# NodoFinalTbeam.net
KiCad netlist of a schematic drawn in Altium Designer
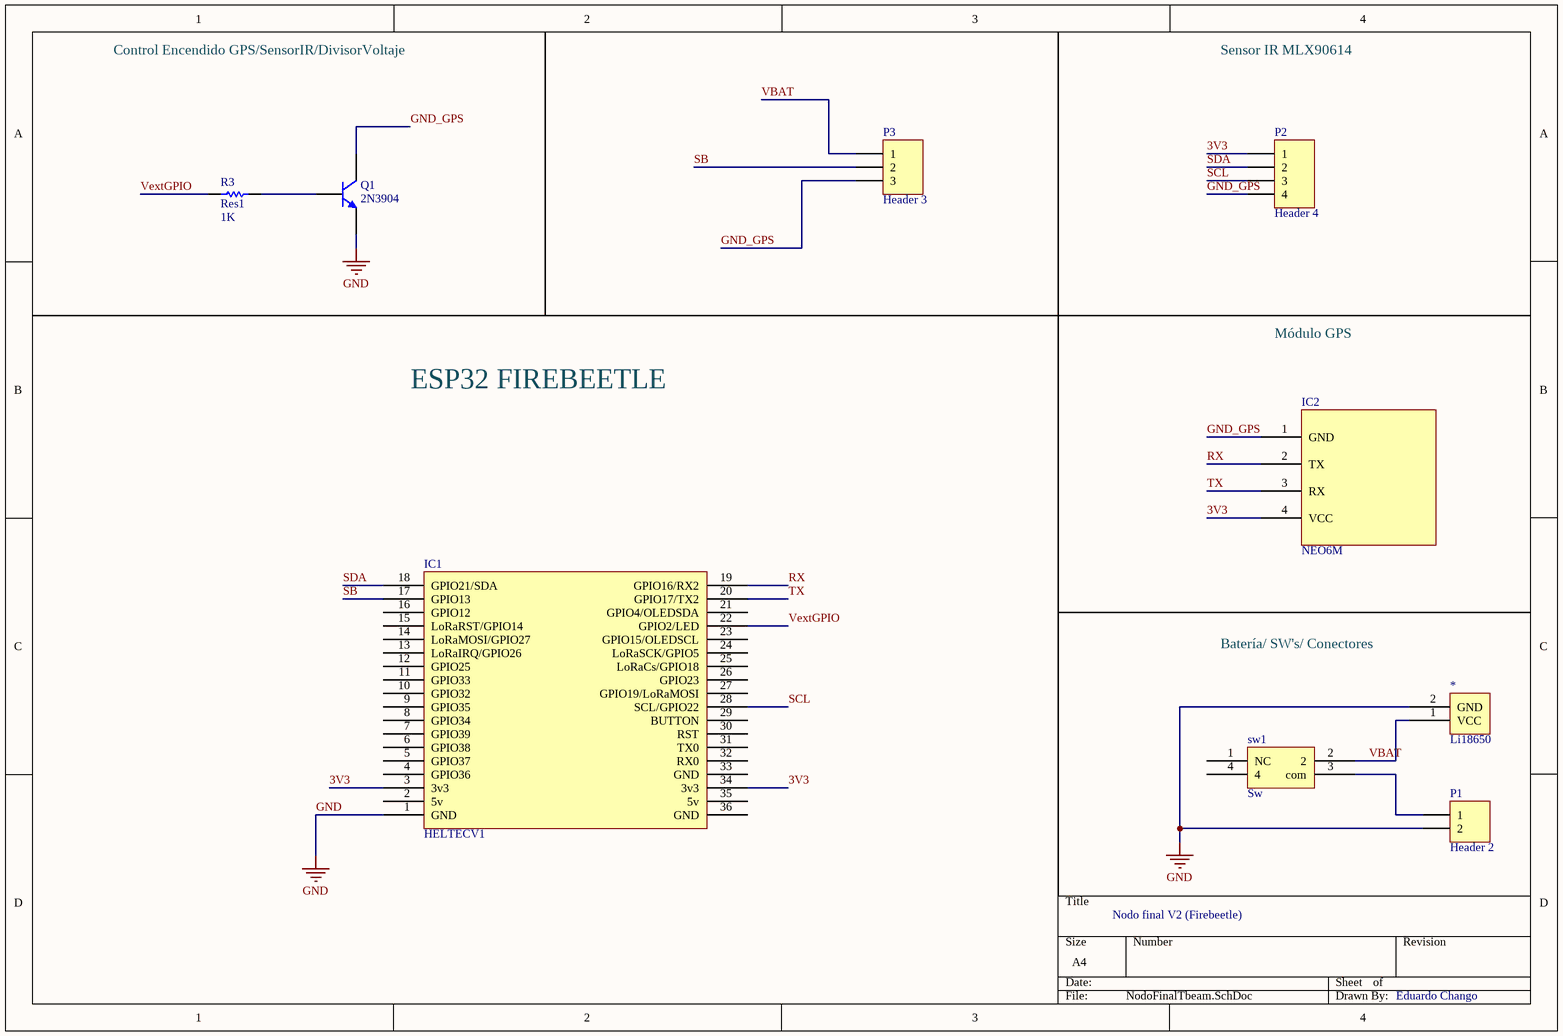
[diagram p0: NodoFinalTbeam.SchDoc]

(export (version "E")
  (design (tool "Eeschema 10.0.6"))
  (components
    (comp (ref "*")
      (value "Li18650")
      (footprint "Li18650")
      (libsource (lib "ComponentesTesis") (part "Li18650"))
    )
    (comp (ref "IC1")
      (value "HELTECV1")
      (footprint "HELTECV1")
      (description "ESP32 LORA BASED MCU")
      (libsource (lib "ComponentesTesis") (part "HELTECV1"))
    )
    (comp (ref "IC2")
      (value "NEO6M")
      (footprint "NEO6M")
      (description "GPS NEO6M")
      (libsource (lib "ComponentesTesis") (part "NEO6M"))
    )
    (comp (ref "P1")
      (value "Header 2")
      (footprint "HDR1X2")
      (description "Header, 2-Pin")
      (fields (field (name "PUBLISHER") "Altium Limited"))
      (libsource (lib "Miscellaneous Connectors") (part "Header 2"))
    )
    (comp (ref "P2")
      (value "Header 4")
      (footprint "HDR1X4")
      (description "Header, 4-Pin")
      (fields (field (name "PUBLISHER") "Altium Limited"))
      (libsource (lib "Miscellaneous Connectors") (part "Header 4"))
    )
    (comp (ref "P3")
      (value "Header 3")
      (footprint "HDR1X3")
      (description "Header, 3-Pin")
      (fields (field (name "PUBLISHER") "Altium Limited"))
      (libsource (lib "Miscellaneous Connectors") (part "Header 3"))
    )
    (comp (ref "Q1")
      (value "2N3904")
      (footprint "TO-92A")
      (description "NPN General Purpose Amplifier")
      (fields (field (name "PUBLISHER") "Altium Limited"))
      (libsource (lib "Miscellaneous Devices") (part "2N3904"))
    )
    (comp (ref "R3")
      (value "Res1")
      (footprint "AXIAL-0.3")
      (description "Resistor")
      (fields (field (name "ALTIUM_VALUE") "1K") (field (name "PUBLISHER") "Altium Limited"))
      (libsource (lib "Miscellaneous Devices") (part "Res1"))
    )
    (comp (ref "sw1")
      (value "Sw")
      (footprint "InterruptorSMD")
      (libsource (lib "ComponentesTesis") (part "Sw"))
    )
  )
  (nets
    (net (code "1") (name "/3V3") (class "Default")
      (node (ref "IC1") (pin "3") (pinfunction "3v3_3") (pintype "power_in"))
      (node (ref "IC1") (pin "34") (pinfunction "3v3_34") (pintype "power_in"))
      (node (ref "IC2") (pin "4") (pinfunction "VCC_4") (pintype "passive"))
      (node (ref "P2") (pin "1") (pinfunction "1_1") (pintype "passive"))
    )
    (net (code "2") (name "/GND_GPS") (class "Default")
      (node (ref "IC2") (pin "1") (pinfunction "GND_1") (pintype "power_in"))
      (node (ref "P2") (pin "4") (pinfunction "4_4") (pintype "passive"))
      (node (ref "P3") (pin "3") (pinfunction "3_3") (pintype "passive"))
      (node (ref "Q1") (pin "3") (pinfunction "C_3") (pintype "passive"))
    )
    (net (code "3") (name "/RX") (class "Default")
      (node (ref "IC1") (pin "19") (pinfunction "GPIO16/RX2_19") (pintype "power_in"))
      (node (ref "IC2") (pin "2") (pinfunction "TX_2") (pintype "passive"))
    )
    (net (code "4") (name "/SB") (class "Default")
      (node (ref "IC1") (pin "17") (pinfunction "GPIO13_17") (pintype "power_in"))
      (node (ref "P3") (pin "2") (pinfunction "2_2") (pintype "passive"))
    )
    (net (code "5") (name "/SCL") (class "Default")
      (node (ref "IC1") (pin "28") (pinfunction "SCL/GPIO22_28") (pintype "power_in"))
      (node (ref "P2") (pin "3") (pinfunction "3_3") (pintype "passive"))
    )
    (net (code "6") (name "/SDA") (class "Default")
      (node (ref "IC1") (pin "18") (pinfunction "GPIO21/SDA_18") (pintype "power_in"))
      (node (ref "P2") (pin "2") (pinfunction "2_2") (pintype "passive"))
    )
    (net (code "7") (name "/TX") (class "Default")
      (node (ref "IC1") (pin "20") (pinfunction "GPIO17/TX2_20") (pintype "power_in"))
      (node (ref "IC2") (pin "3") (pinfunction "RX_3") (pintype "passive"))
    )
    (net (code "8") (name "/VBAT") (class "Default")
      (node (ref "*") (pin "1") (pinfunction "VCC_1") (pintype "power_in"))
      (node (ref "P3") (pin "1") (pinfunction "1_1") (pintype "passive"))
      (node (ref "sw1") (pin "2") (pinfunction "2_2") (pintype "passive"))
    )
    (net (code "9") (name "/VextGPIO") (class "Default")
      (node (ref "IC1") (pin "22") (pinfunction "GPIO2/LED_22") (pintype "power_in"))
      (node (ref "R3") (pin "2") (pinfunction "2_2") (pintype "passive"))
    )
    (net (code "10") (name "GND") (class "Default")
      (node (ref "*") (pin "2") (pinfunction "GND_2") (pintype "passive"))
      (node (ref "IC1") (pin "1") (pinfunction "GND_1") (pintype "power_in"))
      (node (ref "P1") (pin "2") (pinfunction "2_2") (pintype "passive"))
      (node (ref "Q1") (pin "1") (pinfunction "E_1") (pintype "passive"))
    )
    (net (code "11") (name "Net-(Q1-B)") (class "Default")
      (node (ref "Q1") (pin "2") (pinfunction "B_2") (pintype "passive"))
      (node (ref "R3") (pin "1") (pinfunction "1_1") (pintype "passive"))
    )
    (net (code "12") (name "Net-(sw1-com)") (class "Default")
      (node (ref "P1") (pin "1") (pinfunction "1_1") (pintype "passive"))
      (node (ref "sw1") (pin "3") (pinfunction "com_3") (pintype "passive"))
    )
    (net (code "13") (name "unconnected-(IC1-5v-Pad2)") (class "Default")
      (node (ref "IC1") (pin "2") (pinfunction "5v_2") (pintype "power_in"))
    )
    (net (code "14") (name "unconnected-(IC1-5v-Pad35)") (class "Default")
      (node (ref "IC1") (pin "35") (pinfunction "5v_35") (pintype "power_in"))
    )
    (net (code "15") (name "unconnected-(IC1-BUTTON-Pad29)") (class "Default")
      (node (ref "IC1") (pin "29") (pinfunction "BUTTON_29") (pintype "power_in"))
    )
    (net (code "16") (name "unconnected-(IC1-GND-Pad33)") (class "Default")
      (node (ref "IC1") (pin "33") (pinfunction "GND_33") (pintype "power_in"))
    )
    (net (code "17") (name "unconnected-(IC1-GND-Pad36)") (class "Default")
      (node (ref "IC1") (pin "36") (pinfunction "GND_36") (pintype "power_in"))
    )
    (net (code "18") (name "unconnected-(IC1-GPIO4{slash}OLEDSDA-Pad21)") (class "Default")
      (node (ref "IC1") (pin "21") (pinfunction "GPIO4/OLEDSDA_21") (pintype "power_in"))
    )
    (net (code "19") (name "unconnected-(IC1-GPIO12-Pad16)") (class "Default")
      (node (ref "IC1") (pin "16") (pinfunction "GPIO12_16") (pintype "power_in"))
    )
    (net (code "20") (name "unconnected-(IC1-GPIO15{slash}OLEDSCL-Pad23)") (class "Default")
      (node (ref "IC1") (pin "23") (pinfunction "GPIO15/OLEDSCL_23") (pintype "power_in"))
    )
    (net (code "21") (name "unconnected-(IC1-GPIO19{slash}LoRaMOSI-Pad27)") (class "Default")
      (node (ref "IC1") (pin "27") (pinfunction "GPIO19/LoRaMOSI_27") (pintype "power_in"))
    )
    (net (code "22") (name "unconnected-(IC1-GPIO23-Pad26)") (class "Default")
      (node (ref "IC1") (pin "26") (pinfunction "GPIO23_26") (pintype "power_in"))
    )
    (net (code "23") (name "unconnected-(IC1-GPIO25-Pad12)") (class "Default")
      (node (ref "IC1") (pin "12") (pinfunction "GPIO25_12") (pintype "power_in"))
    )
    (net (code "24") (name "unconnected-(IC1-GPIO32-Pad10)") (class "Default")
      (node (ref "IC1") (pin "10") (pinfunction "GPIO32_10") (pintype "power_in"))
    )
    (net (code "25") (name "unconnected-(IC1-GPIO33-Pad11)") (class "Default")
      (node (ref "IC1") (pin "11") (pinfunction "GPIO33_11") (pintype "power_in"))
    )
    (net (code "26") (name "unconnected-(IC1-GPIO34-Pad8)") (class "Default")
      (node (ref "IC1") (pin "8") (pinfunction "GPIO34_8") (pintype "power_in"))
    )
    (net (code "27") (name "unconnected-(IC1-GPIO35-Pad9)") (class "Default")
      (node (ref "IC1") (pin "9") (pinfunction "GPIO35_9") (pintype "power_in"))
    )
    (net (code "28") (name "unconnected-(IC1-GPIO36-Pad4)") (class "Default")
      (node (ref "IC1") (pin "4") (pinfunction "GPIO36_4") (pintype "power_in"))
    )
    (net (code "29") (name "unconnected-(IC1-GPIO37-Pad5)") (class "Default")
      (node (ref "IC1") (pin "5") (pinfunction "GPIO37_5") (pintype "power_in"))
    )
    (net (code "30") (name "unconnected-(IC1-GPIO38-Pad6)") (class "Default")
      (node (ref "IC1") (pin "6") (pinfunction "GPIO38_6") (pintype "power_in"))
    )
    (net (code "31") (name "unconnected-(IC1-GPIO39-Pad7)") (class "Default")
      (node (ref "IC1") (pin "7") (pinfunction "GPIO39_7") (pintype "power_in"))
    )
    (net (code "32") (name "unconnected-(IC1-LoRaCs{slash}GPIO18-Pad25)") (class "Default")
      (node (ref "IC1") (pin "25") (pinfunction "LoRaCs/GPIO18_25") (pintype "power_in"))
    )
    (net (code "33") (name "unconnected-(IC1-LoRaIRQ{slash}GPIO26-Pad13)") (class "Default")
      (node (ref "IC1") (pin "13") (pinfunction "LoRaIRQ/GPIO26_13") (pintype "power_in"))
    )
    (net (code "34") (name "unconnected-(IC1-LoRaMOSI{slash}GPIO27-Pad14)") (class "Default")
      (node (ref "IC1") (pin "14") (pinfunction "LoRaMOSI/GPIO27_14") (pintype "power_in"))
    )
    (net (code "35") (name "unconnected-(IC1-LoRaRST{slash}GPIO14-Pad15)") (class "Default")
      (node (ref "IC1") (pin "15") (pinfunction "LoRaRST/GPIO14_15") (pintype "power_in"))
    )
    (net (code "36") (name "unconnected-(IC1-LoRaSCK{slash}GPIO5-Pad24)") (class "Default")
      (node (ref "IC1") (pin "24") (pinfunction "LoRaSCK/GPIO5_24") (pintype "power_in"))
    )
    (net (code "37") (name "unconnected-(IC1-RST-Pad30)") (class "Default")
      (node (ref "IC1") (pin "30") (pinfunction "RST_30") (pintype "power_in"))
    )
    (net (code "38") (name "unconnected-(IC1-RX0-Pad32)") (class "Default")
      (node (ref "IC1") (pin "32") (pinfunction "RX0_32") (pintype "power_in"))
    )
    (net (code "39") (name "unconnected-(IC1-TX0-Pad31)") (class "Default")
      (node (ref "IC1") (pin "31") (pinfunction "TX0_31") (pintype "power_in"))
    )
    (net (code "40") (name "unconnected-(sw1-NC-Pad1)") (class "Default")
      (node (ref "sw1") (pin "1") (pinfunction "NC_1") (pintype "passive"))
    )
    (net (code "41") (name "unconnected-(sw1-Pad4)") (class "Default")
      (node (ref "sw1") (pin "4") (pinfunction "4_4") (pintype "passive"))
    )
  )
)
